# NTC.net
KiCad netlist of a schematic drawn in Altium Designer
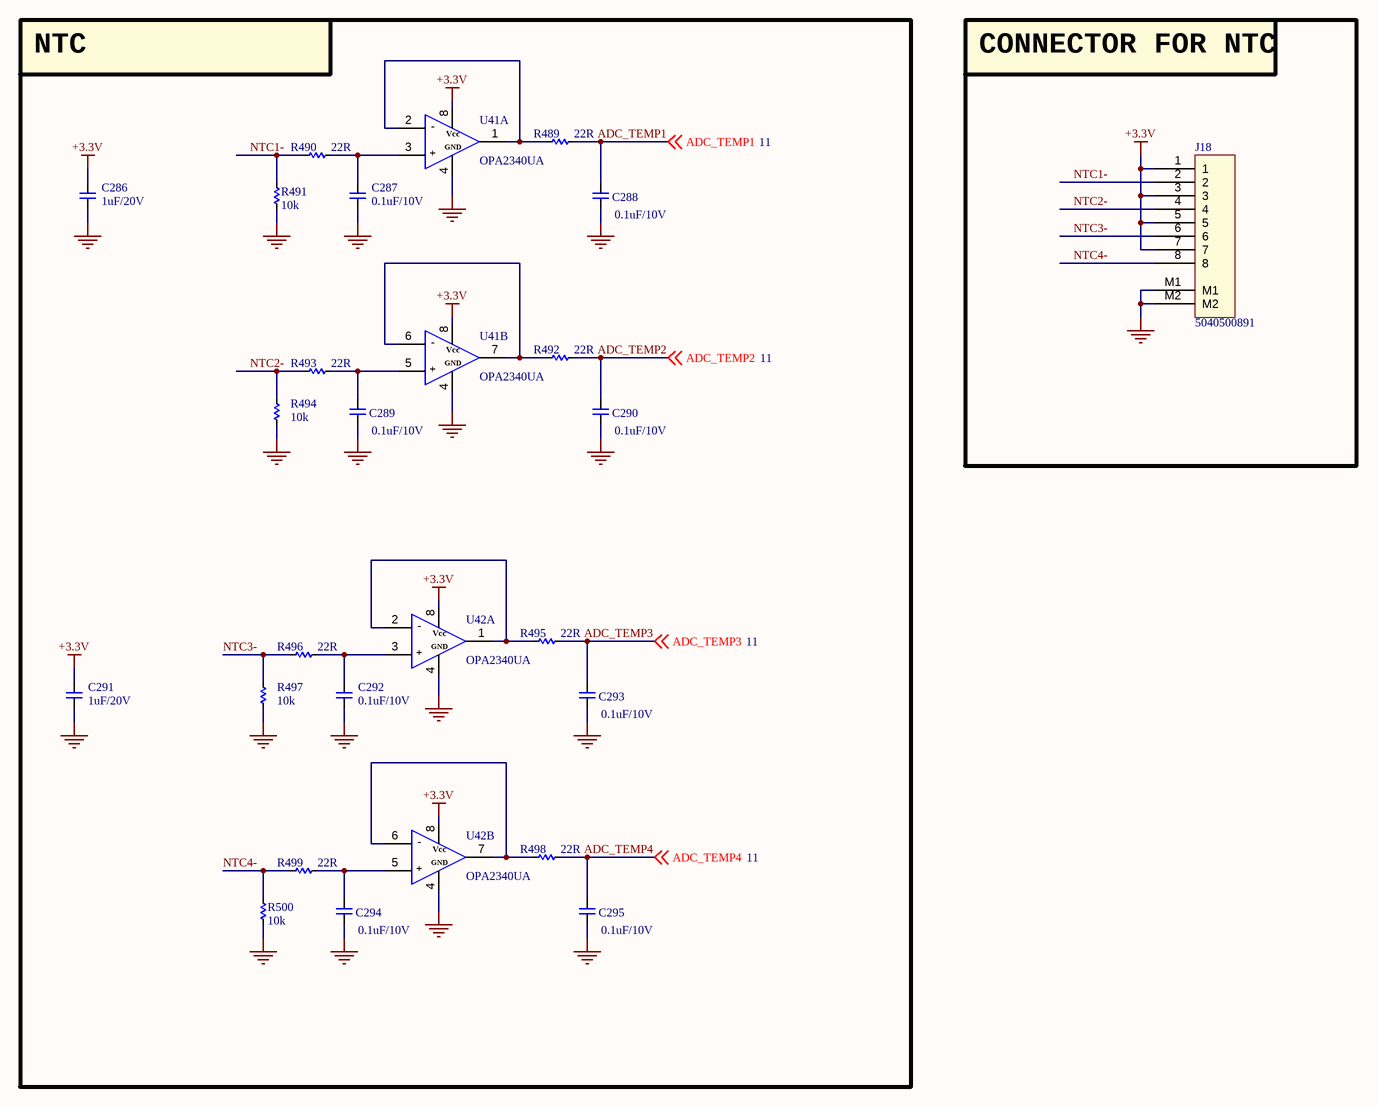
[diagram p0: NTC.SchDoc]

(export (version "E")
  (design (tool "Eeschema 10.0.6"))
  (components
    (comp (ref "C286")
      (value "1uF/20V")
      (footprint "CAP_C_1005X60")
      (description "CAP")
      (libsource (lib "LABLIB") (part "_CAP_C_2"))
    )
    (comp (ref "C287")
      (value "0.1uF/10V")
      (footprint "CAP_C_1005X50_L")
      (description "CAP")
      (libsource (lib "LABLIB") (part "_CAP_C_2"))
    )
    (comp (ref "C288")
      (value "0.1uF/10V")
      (footprint "CAP_C_1005X50_L")
      (description "CAP")
      (libsource (lib "LABLIB") (part "_CAP_C_2"))
    )
    (comp (ref "C289")
      (value "0.1uF/10V")
      (footprint "CAP_C_1005X50_L")
      (description "CAP")
      (libsource (lib "LABLIB") (part "_CAP_C_2"))
    )
    (comp (ref "C290")
      (value "0.1uF/10V")
      (footprint "CAP_C_1005X50_L")
      (description "CAP")
      (libsource (lib "LABLIB") (part "_CAP_C_2"))
    )
    (comp (ref "C291")
      (value "1uF/20V")
      (footprint "CAP_C_1005X60")
      (description "CAP")
      (libsource (lib "LABLIB") (part "_CAP_C_2"))
    )
    (comp (ref "C292")
      (value "0.1uF/10V")
      (footprint "CAP_C_1005X50_L")
      (description "CAP")
      (libsource (lib "LABLIB") (part "_CAP_C_2"))
    )
    (comp (ref "C293")
      (value "0.1uF/10V")
      (footprint "CAP_C_1005X50_L")
      (description "CAP")
      (libsource (lib "LABLIB") (part "_CAP_C_2"))
    )
    (comp (ref "C294")
      (value "0.1uF/10V")
      (footprint "CAP_C_1005X50_L")
      (description "CAP")
      (libsource (lib "LABLIB") (part "_CAP_C_2"))
    )
    (comp (ref "C295")
      (value "0.1uF/10V")
      (footprint "CAP_C_1005X50_L")
      (description "CAP")
      (libsource (lib "LABLIB") (part "_CAP_C_2"))
    )
    (comp (ref "J18")
      (value "5040500891")
      (footprint "MOLEX_5040500891")
      (libsource (lib "LABLIB") (part "Header 8x1_2M"))
    )
    (comp (ref "R489")
      (value "22R")
      (footprint "RES_C_1005X40")
      (description "RES")
      (libsource (lib "LABLIB") (part "_RES_B_2"))
    )
    (comp (ref "R490")
      (value "22R")
      (footprint "RES_C_1005X40")
      (description "RES")
      (libsource (lib "LABLIB") (part "_RES_B_2"))
    )
    (comp (ref "R491")
      (value "10k")
      (footprint "RES_C_1005X40")
      (description "RES")
      (libsource (lib "LABLIB") (part "_RES_B_2"))
    )
    (comp (ref "R492")
      (value "22R")
      (footprint "RES_C_1005X40")
      (description "RES")
      (libsource (lib "LABLIB") (part "_RES_B_2"))
    )
    (comp (ref "R493")
      (value "22R")
      (footprint "RES_C_1005X40")
      (description "RES")
      (libsource (lib "LABLIB") (part "_RES_B_2"))
    )
    (comp (ref "R494")
      (value "10k")
      (footprint "RES_C_1005X40")
      (description "RES")
      (libsource (lib "LABLIB") (part "_RES_B_2"))
    )
    (comp (ref "R495")
      (value "22R")
      (footprint "RES_C_1005X40")
      (description "RES")
      (libsource (lib "LABLIB") (part "_RES_B_2"))
    )
    (comp (ref "R496")
      (value "22R")
      (footprint "RES_C_1005X40")
      (description "RES")
      (libsource (lib "LABLIB") (part "_RES_B_2"))
    )
    (comp (ref "R497")
      (value "10k")
      (footprint "RES_C_1005X40")
      (description "RES")
      (libsource (lib "LABLIB") (part "_RES_B_2"))
    )
    (comp (ref "R498")
      (value "22R")
      (footprint "RES_C_1005X40")
      (description "RES")
      (libsource (lib "LABLIB") (part "_RES_B_2"))
    )
    (comp (ref "R499")
      (value "22R")
      (footprint "RES_C_1005X40")
      (description "RES")
      (libsource (lib "LABLIB") (part "_RES_B_2"))
    )
    (comp (ref "R500")
      (value "10k")
      (footprint "RES_C_1005X40")
      (description "RES")
      (libsource (lib "LABLIB") (part "_RES_B_2"))
    )
    (comp (ref "U41")
      (value "OPA2340UA")
      (footprint "SOIC127P602X173-8N")
      (libsource (lib "EXP_HW_V3") (part "OPA2340UA"))
    )
    (comp (ref "U42")
      (value "OPA2340UA")
      (footprint "SOIC127P602X173-8N")
      (libsource (lib "EXP_HW_V3") (part "OPA2340UA"))
    )
  )
  (nets
    (net (code "1") (name "+3.3V") (class "Default")
      (node (ref "C286") (pin "2") (pinfunction "2_2") (pintype "passive"))
      (node (ref "C291") (pin "2") (pinfunction "2_2") (pintype "passive"))
      (node (ref "J18") (pin "1") (pinfunction "1_1") (pintype "passive"))
      (node (ref "J18") (pin "3") (pinfunction "3_3") (pintype "passive"))
      (node (ref "J18") (pin "5") (pinfunction "5_5") (pintype "passive"))
      (node (ref "J18") (pin "7") (pinfunction "7_7") (pintype "passive"))
      (node (ref "U41") (pin "8") (pinfunction "8_8") (pintype "passive"))
      (node (ref "U42") (pin "8") (pinfunction "8_8") (pintype "passive"))
    )
    (net (code "2") (name "/NTC1-") (class "Default")
      (node (ref "J18") (pin "2") (pinfunction "2_2") (pintype "passive"))
      (node (ref "R490") (pin "1") (pinfunction "1_1") (pintype "passive"))
      (node (ref "R491") (pin "2") (pinfunction "2_2") (pintype "passive"))
    )
    (net (code "3") (name "/NTC2-") (class "Default")
      (node (ref "J18") (pin "4") (pinfunction "4_4") (pintype "passive"))
      (node (ref "R493") (pin "1") (pinfunction "1_1") (pintype "passive"))
      (node (ref "R494") (pin "2") (pinfunction "2_2") (pintype "passive"))
    )
    (net (code "4") (name "/NTC3-") (class "Default")
      (node (ref "J18") (pin "6") (pinfunction "6_6") (pintype "passive"))
      (node (ref "R496") (pin "1") (pinfunction "1_1") (pintype "passive"))
      (node (ref "R497") (pin "2") (pinfunction "2_2") (pintype "passive"))
    )
    (net (code "5") (name "/NTC4-") (class "Default")
      (node (ref "J18") (pin "8") (pinfunction "8_8") (pintype "passive"))
      (node (ref "R499") (pin "1") (pinfunction "1_1") (pintype "passive"))
      (node (ref "R500") (pin "2") (pinfunction "2_2") (pintype "passive"))
    )
    (net (code "6") (name "ADC_TEMP1") (class "Default")
      (node (ref "C288") (pin "2") (pinfunction "2_2") (pintype "passive"))
      (node (ref "R489") (pin "2") (pinfunction "2_2") (pintype "passive"))
    )
    (net (code "7") (name "ADC_TEMP2") (class "Default")
      (node (ref "C290") (pin "2") (pinfunction "2_2") (pintype "passive"))
      (node (ref "R492") (pin "2") (pinfunction "2_2") (pintype "passive"))
    )
    (net (code "8") (name "ADC_TEMP3") (class "Default")
      (node (ref "C293") (pin "2") (pinfunction "2_2") (pintype "passive"))
      (node (ref "R495") (pin "2") (pinfunction "2_2") (pintype "passive"))
    )
    (net (code "9") (name "ADC_TEMP4") (class "Default")
      (node (ref "C295") (pin "2") (pinfunction "2_2") (pintype "passive"))
      (node (ref "R498") (pin "2") (pinfunction "2_2") (pintype "passive"))
    )
    (net (code "10") (name "GND") (class "Default")
      (node (ref "C286") (pin "1") (pinfunction "1_1") (pintype "passive"))
      (node (ref "C287") (pin "1") (pinfunction "1_1") (pintype "passive"))
      (node (ref "C288") (pin "1") (pinfunction "1_1") (pintype "passive"))
      (node (ref "C289") (pin "1") (pinfunction "1_1") (pintype "passive"))
      (node (ref "C290") (pin "1") (pinfunction "1_1") (pintype "passive"))
      (node (ref "C291") (pin "1") (pinfunction "1_1") (pintype "passive"))
      (node (ref "C292") (pin "1") (pinfunction "1_1") (pintype "passive"))
      (node (ref "C293") (pin "1") (pinfunction "1_1") (pintype "passive"))
      (node (ref "C294") (pin "1") (pinfunction "1_1") (pintype "passive"))
      (node (ref "C295") (pin "1") (pinfunction "1_1") (pintype "passive"))
      (node (ref "J18") (pin "M1") (pinfunction "M1_M1") (pintype "passive"))
      (node (ref "J18") (pin "M2") (pinfunction "M2_M2") (pintype "passive"))
      (node (ref "R491") (pin "1") (pinfunction "1_1") (pintype "passive"))
      (node (ref "R494") (pin "1") (pinfunction "1_1") (pintype "passive"))
      (node (ref "R497") (pin "1") (pinfunction "1_1") (pintype "passive"))
      (node (ref "R500") (pin "1") (pinfunction "1_1") (pintype "passive"))
      (node (ref "U41") (pin "4") (pinfunction "4_4") (pintype "passive"))
      (node (ref "U42") (pin "4") (pinfunction "4_4") (pintype "passive"))
    )
    (net (code "11") (name "Net-(C287-Pad2)") (class "Default")
      (node (ref "C287") (pin "2") (pinfunction "2_2") (pintype "passive"))
      (node (ref "R490") (pin "2") (pinfunction "2_2") (pintype "passive"))
      (node (ref "U41") (pin "3") (pinfunction "3_3") (pintype "passive"))
    )
    (net (code "12") (name "Net-(C289-Pad2)") (class "Default")
      (node (ref "C289") (pin "2") (pinfunction "2_2") (pintype "passive"))
      (node (ref "R493") (pin "2") (pinfunction "2_2") (pintype "passive"))
      (node (ref "U41") (pin "5") (pinfunction "5_5") (pintype "passive"))
    )
    (net (code "13") (name "Net-(C292-Pad2)") (class "Default")
      (node (ref "C292") (pin "2") (pinfunction "2_2") (pintype "passive"))
      (node (ref "R496") (pin "2") (pinfunction "2_2") (pintype "passive"))
      (node (ref "U42") (pin "3") (pinfunction "3_3") (pintype "passive"))
    )
    (net (code "14") (name "Net-(C294-Pad2)") (class "Default")
      (node (ref "C294") (pin "2") (pinfunction "2_2") (pintype "passive"))
      (node (ref "R499") (pin "2") (pinfunction "2_2") (pintype "passive"))
      (node (ref "U42") (pin "5") (pinfunction "5_5") (pintype "passive"))
    )
    (net (code "15") (name "Net-(R489-Pad1)") (class "Default")
      (node (ref "R489") (pin "1") (pinfunction "1_1") (pintype "passive"))
      (node (ref "U41") (pin "1") (pinfunction "1_1") (pintype "passive"))
      (node (ref "U41") (pin "2") (pinfunction "2_2") (pintype "passive"))
    )
    (net (code "16") (name "Net-(R492-Pad1)") (class "Default")
      (node (ref "R492") (pin "1") (pinfunction "1_1") (pintype "passive"))
      (node (ref "U41") (pin "6") (pinfunction "6_6") (pintype "passive"))
      (node (ref "U41") (pin "7") (pinfunction "7_7") (pintype "passive"))
    )
    (net (code "17") (name "Net-(R495-Pad1)") (class "Default")
      (node (ref "R495") (pin "1") (pinfunction "1_1") (pintype "passive"))
      (node (ref "U42") (pin "1") (pinfunction "1_1") (pintype "passive"))
      (node (ref "U42") (pin "2") (pinfunction "2_2") (pintype "passive"))
    )
    (net (code "18") (name "Net-(R498-Pad1)") (class "Default")
      (node (ref "R498") (pin "1") (pinfunction "1_1") (pintype "passive"))
      (node (ref "U42") (pin "6") (pinfunction "6_6") (pintype "passive"))
      (node (ref "U42") (pin "7") (pinfunction "7_7") (pintype "passive"))
    )
  )
)
